# pcb.net
KiCad netlist of a schematic drawn in EAGLE
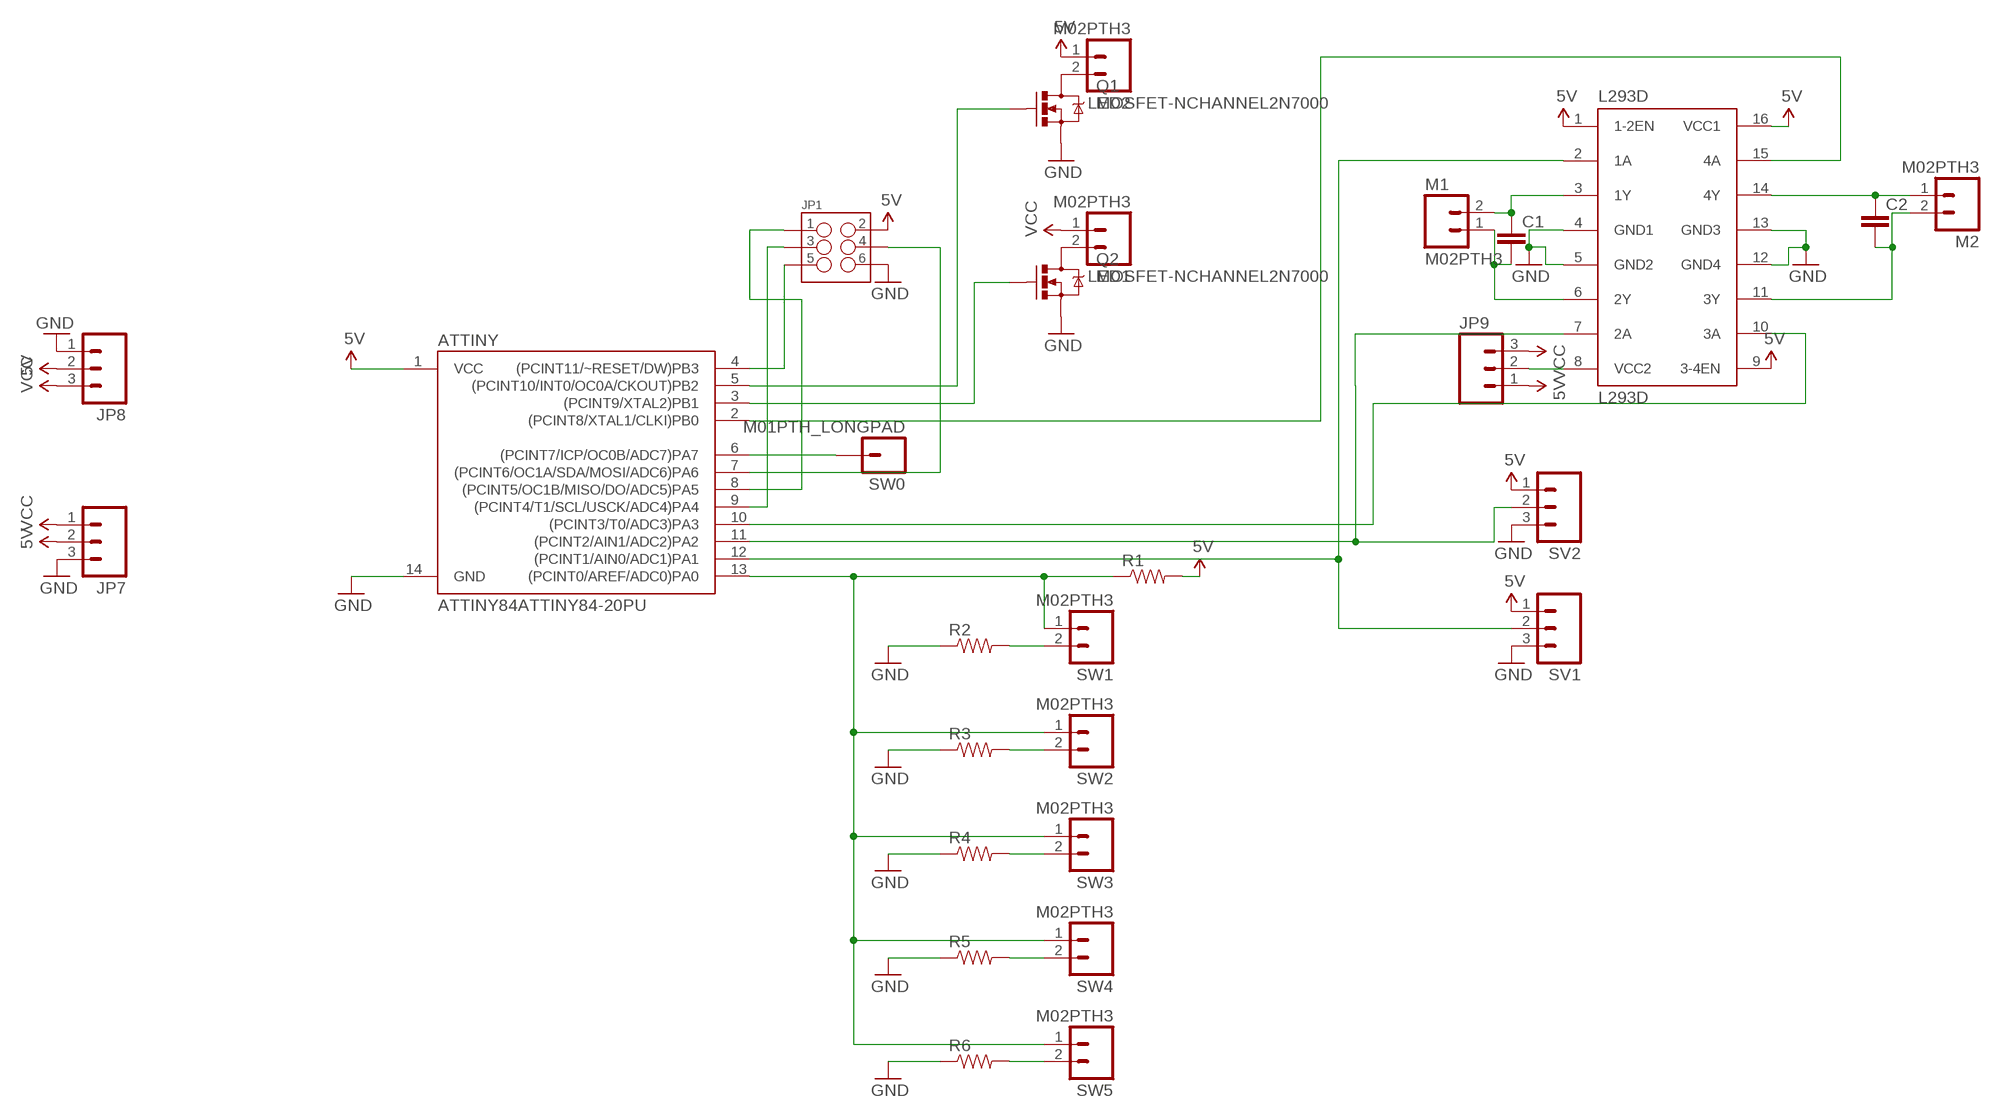
[diagram p0: schematic, sheet 1]

(export (version "E")
  (design (tool "Eeschema 10.0.6"))
  (components
    (comp (ref "ATTINY")
      (value "ATTINY84ATTINY84-20PU")
      (footprint "eagle-import:DIL14")
      (libsource (lib "eagle-import") (part "ATTINY84ATTINY84-20PU"))
    )
    (comp (ref "C1")
      (value "CAPPTH")
      (footprint "eagle-import:CAP-PTH-SMALL")
      (libsource (lib "eagle-import") (part "CAPPTH"))
    )
    (comp (ref "C2")
      (value "CAPPTH")
      (footprint "eagle-import:CAP-PTH-SMALL")
      (libsource (lib "eagle-import") (part "CAPPTH"))
    )
    (comp (ref "JP1")
      (value "M03X22X3_SILK_MALE_PTH")
      (footprint "eagle-import:2X3")
      (libsource (lib "eagle-import") (part "M03X22X3_SILK_MALE_PTH"))
    )
    (comp (ref "JP7")
      (value "M03SCREW")
      (footprint "eagle-import:SCREWTERMINAL-3.5MM-3")
      (libsource (lib "eagle-import") (part "M03SCREW"))
    )
    (comp (ref "JP8")
      (value "M03SCREW")
      (footprint "eagle-import:SCREWTERMINAL-3.5MM-3")
      (libsource (lib "eagle-import") (part "M03SCREW"))
    )
    (comp (ref "JP9")
      (value "M03LONGPADS")
      (footprint "eagle-import:1X03_LONGPADS")
      (libsource (lib "eagle-import") (part "M03LONGPADS"))
    )
    (comp (ref "L293D")
      (value "L293D")
      (footprint "eagle-import:DIL16")
      (libsource (lib "eagle-import") (part "L293D"))
    )
    (comp (ref "LED1")
      (value "M02PTH3")
      (footprint "eagle-import:1X02_LONGPADS")
      (libsource (lib "eagle-import") (part "M02PTH3"))
    )
    (comp (ref "LED2")
      (value "M02PTH3")
      (footprint "eagle-import:1X02_LONGPADS")
      (libsource (lib "eagle-import") (part "M02PTH3"))
    )
    (comp (ref "M1")
      (value "M02PTH3")
      (footprint "eagle-import:1X02_LONGPADS")
      (libsource (lib "eagle-import") (part "M02PTH3"))
    )
    (comp (ref "M2")
      (value "M02PTH3")
      (footprint "eagle-import:1X02_LONGPADS")
      (libsource (lib "eagle-import") (part "M02PTH3"))
    )
    (comp (ref "Q1")
      (value "MOSFET-NCHANNEL2N7000")
      (footprint "eagle-import:TO-92")
      (libsource (lib "eagle-import") (part "MOSFET-NCHANNEL2N7000"))
    )
    (comp (ref "Q2")
      (value "MOSFET-NCHANNEL2N7000")
      (footprint "eagle-import:TO-92")
      (libsource (lib "eagle-import") (part "MOSFET-NCHANNEL2N7000"))
    )
    (comp (ref "R1")
      (value "RESISTORPTH-1/4W")
      (footprint "eagle-import:AXIAL-0.4")
      (libsource (lib "eagle-import") (part "RESISTORPTH-1/4W"))
    )
    (comp (ref "R2")
      (value "RESISTORPTH-1/4W")
      (footprint "eagle-import:AXIAL-0.4")
      (libsource (lib "eagle-import") (part "RESISTORPTH-1/4W"))
    )
    (comp (ref "R3")
      (value "RESISTORPTH-1/4W")
      (footprint "eagle-import:AXIAL-0.4")
      (libsource (lib "eagle-import") (part "RESISTORPTH-1/4W"))
    )
    (comp (ref "R4")
      (value "RESISTORPTH-1/4W")
      (footprint "eagle-import:AXIAL-0.4")
      (libsource (lib "eagle-import") (part "RESISTORPTH-1/4W"))
    )
    (comp (ref "R5")
      (value "RESISTORPTH-1/4W")
      (footprint "eagle-import:AXIAL-0.4")
      (libsource (lib "eagle-import") (part "RESISTORPTH-1/4W"))
    )
    (comp (ref "R6")
      (value "RESISTORPTH-1/4W")
      (footprint "eagle-import:AXIAL-0.4")
      (libsource (lib "eagle-import") (part "RESISTORPTH-1/4W"))
    )
    (comp (ref "SV1")
      (value "M03LONGPADS")
      (footprint "eagle-import:1X03_LONGPADS")
      (libsource (lib "eagle-import") (part "M03LONGPADS"))
    )
    (comp (ref "SV2")
      (value "M03LONGPADS")
      (footprint "eagle-import:1X03_LONGPADS")
      (libsource (lib "eagle-import") (part "M03LONGPADS"))
    )
    (comp (ref "SW0")
      (value "M01PTH_LONGPAD")
      (footprint "eagle-import:1X01_LONGPAD")
      (libsource (lib "eagle-import") (part "M01PTH_LONGPAD"))
    )
    (comp (ref "SW1")
      (value "M02PTH3")
      (footprint "eagle-import:1X02_LONGPADS")
      (libsource (lib "eagle-import") (part "M02PTH3"))
    )
    (comp (ref "SW2")
      (value "M02PTH3")
      (footprint "eagle-import:1X02_LONGPADS")
      (libsource (lib "eagle-import") (part "M02PTH3"))
    )
    (comp (ref "SW3")
      (value "M02PTH3")
      (footprint "eagle-import:1X02_LONGPADS")
      (libsource (lib "eagle-import") (part "M02PTH3"))
    )
    (comp (ref "SW4")
      (value "M02PTH3")
      (footprint "eagle-import:1X02_LONGPADS")
      (libsource (lib "eagle-import") (part "M02PTH3"))
    )
    (comp (ref "SW5")
      (value "M02PTH3")
      (footprint "eagle-import:1X02_LONGPADS")
      (libsource (lib "eagle-import") (part "M02PTH3"))
    )
  )
  (nets
    (net (code "1") (name "5V") (class "Default")
      (node (ref "ATTINY") (pin "1") (pinfunction "VCC_1") (pintype "bidirectional"))
      (node (ref "JP1") (pin "2") (pinfunction "2_2") (pintype "bidirectional"))
      (node (ref "JP7") (pin "2") (pinfunction "2_2") (pintype "passive"))
      (node (ref "JP8") (pin "2") (pinfunction "2_2") (pintype "passive"))
      (node (ref "JP9") (pin "1") (pinfunction "1_1") (pintype "passive"))
      (node (ref "L293D") (pin "1") (pinfunction "1-2EN_1") (pintype "input"))
      (node (ref "L293D") (pin "16") (pinfunction "VCC1_16") (pintype "power_in"))
      (node (ref "L293D") (pin "9") (pinfunction "3-4EN_9") (pintype "input"))
      (node (ref "LED2") (pin "1") (pinfunction "1_1") (pintype "passive"))
      (node (ref "R1") (pin "P$2") (pinfunction "2_P$2") (pintype "passive"))
      (node (ref "SV1") (pin "1") (pinfunction "1_1") (pintype "passive"))
      (node (ref "SV2") (pin "1") (pinfunction "1_1") (pintype "passive"))
    )
    (net (code "2") (name "GND") (class "Default")
      (node (ref "ATTINY") (pin "14") (pinfunction "GND_14") (pintype "bidirectional"))
      (node (ref "JP1") (pin "6") (pinfunction "6_6") (pintype "bidirectional"))
      (node (ref "JP7") (pin "3") (pinfunction "3_3") (pintype "passive"))
      (node (ref "JP8") (pin "1") (pinfunction "1_1") (pintype "passive"))
      (node (ref "L293D") (pin "12") (pinfunction "GND4_12") (pintype "power_in"))
      (node (ref "L293D") (pin "13") (pinfunction "GND3_13") (pintype "power_in"))
      (node (ref "L293D") (pin "4") (pinfunction "GND1_4") (pintype "power_in"))
      (node (ref "L293D") (pin "5") (pinfunction "GND2_5") (pintype "power_in"))
      (node (ref "Q1") (pin "1") (pinfunction "S_1") (pintype "passive"))
      (node (ref "Q2") (pin "1") (pinfunction "S_1") (pintype "passive"))
      (node (ref "R2") (pin "P$1") (pinfunction "1_P$1") (pintype "passive"))
      (node (ref "R3") (pin "P$1") (pinfunction "1_P$1") (pintype "passive"))
      (node (ref "R4") (pin "P$1") (pinfunction "1_P$1") (pintype "passive"))
      (node (ref "R5") (pin "P$1") (pinfunction "1_P$1") (pintype "passive"))
      (node (ref "R6") (pin "P$1") (pinfunction "1_P$1") (pintype "passive"))
      (node (ref "SV1") (pin "3") (pinfunction "3_3") (pintype "passive"))
      (node (ref "SV2") (pin "3") (pinfunction "3_3") (pintype "passive"))
    )
    (net (code "3") (name "Net-(ATTINY-(PCINT0{slash}AREF{slash}ADC0)PA0)") (class "Default")
      (node (ref "ATTINY") (pin "13") (pinfunction "(PCINT0/AREF/ADC0)PA0_13") (pintype "bidirectional"))
      (node (ref "R1") (pin "P$1") (pinfunction "1_P$1") (pintype "passive"))
      (node (ref "SW1") (pin "1") (pinfunction "1_1") (pintype "passive"))
      (node (ref "SW2") (pin "1") (pinfunction "1_1") (pintype "passive"))
      (node (ref "SW3") (pin "1") (pinfunction "1_1") (pintype "passive"))
      (node (ref "SW4") (pin "1") (pinfunction "1_1") (pintype "passive"))
      (node (ref "SW5") (pin "1") (pinfunction "1_1") (pintype "passive"))
    )
    (net (code "4") (name "Net-(ATTINY-(PCINT1{slash}AIN0{slash}ADC1)PA1)") (class "Default")
      (node (ref "ATTINY") (pin "12") (pinfunction "(PCINT1/AIN0/ADC1)PA1_12") (pintype "bidirectional"))
      (node (ref "L293D") (pin "2") (pinfunction "1A_2") (pintype "input"))
      (node (ref "SV1") (pin "2") (pinfunction "2_2") (pintype "passive"))
    )
    (net (code "5") (name "Net-(ATTINY-(PCINT2{slash}AIN1{slash}ADC2)PA2)") (class "Default")
      (node (ref "ATTINY") (pin "11") (pinfunction "(PCINT2/AIN1/ADC2)PA2_11") (pintype "bidirectional"))
      (node (ref "L293D") (pin "7") (pinfunction "2A_7") (pintype "input"))
      (node (ref "SV2") (pin "2") (pinfunction "2_2") (pintype "passive"))
    )
    (net (code "6") (name "Net-(ATTINY-(PCINT3{slash}T0{slash}ADC3)PA3)") (class "Default")
      (node (ref "ATTINY") (pin "10") (pinfunction "(PCINT3/T0/ADC3)PA3_10") (pintype "bidirectional"))
      (node (ref "L293D") (pin "10") (pinfunction "3A_10") (pintype "input"))
    )
    (net (code "7") (name "Net-(ATTINY-(PCINT4{slash}T1{slash}SCL{slash}USCK{slash}ADC4)PA4)") (class "Default")
      (node (ref "ATTINY") (pin "9") (pinfunction "(PCINT4/T1/SCL/USCK/ADC4)PA4_9") (pintype "bidirectional"))
      (node (ref "JP1") (pin "3") (pinfunction "3_3") (pintype "bidirectional"))
    )
    (net (code "8") (name "Net-(ATTINY-(PCINT5{slash}OC1B{slash}MISO{slash}DO{slash}ADC5)PA5)") (class "Default")
      (node (ref "ATTINY") (pin "8") (pinfunction "(PCINT5/OC1B/MISO/DO/ADC5)PA5_8") (pintype "bidirectional"))
      (node (ref "JP1") (pin "1") (pinfunction "1_1") (pintype "bidirectional"))
    )
    (net (code "9") (name "Net-(ATTINY-(PCINT6{slash}OC1A{slash}SDA{slash}MOSI{slash}ADC6)PA6)") (class "Default")
      (node (ref "ATTINY") (pin "7") (pinfunction "(PCINT6/OC1A/SDA/MOSI/ADC6)PA6_7") (pintype "bidirectional"))
      (node (ref "JP1") (pin "4") (pinfunction "4_4") (pintype "bidirectional"))
    )
    (net (code "10") (name "Net-(ATTINY-(PCINT7{slash}ICP{slash}OC0B{slash}ADC7)PA7)") (class "Default")
      (node (ref "ATTINY") (pin "6") (pinfunction "(PCINT7/ICP/OC0B/ADC7)PA7_6") (pintype "bidirectional"))
      (node (ref "SW0") (pin "1") (pinfunction "1_1") (pintype "passive"))
    )
    (net (code "11") (name "Net-(ATTINY-(PCINT8{slash}XTAL1{slash}CLKI)PB0)") (class "Default")
      (node (ref "ATTINY") (pin "2") (pinfunction "(PCINT8/XTAL1/CLKI)PB0_2") (pintype "bidirectional"))
      (node (ref "L293D") (pin "15") (pinfunction "4A_15") (pintype "input"))
    )
    (net (code "12") (name "Net-(ATTINY-(PCINT9{slash}XTAL2)PB1)") (class "Default")
      (node (ref "ATTINY") (pin "3") (pinfunction "(PCINT9/XTAL2)PB1_3") (pintype "bidirectional"))
      (node (ref "Q2") (pin "2") (pinfunction "G_2") (pintype "passive"))
    )
    (net (code "13") (name "Net-(ATTINY-(PCINT10{slash}INT0{slash}OC0A{slash}CKOUT)PB2)") (class "Default")
      (node (ref "ATTINY") (pin "5") (pinfunction "(PCINT10/INT0/OC0A/CKOUT)PB2_5") (pintype "bidirectional"))
      (node (ref "Q1") (pin "2") (pinfunction "G_2") (pintype "passive"))
    )
    (net (code "14") (name "Net-(ATTINY-(PCINT11{slash}~{RESET{slash}DW})PB3)") (class "Default")
      (node (ref "ATTINY") (pin "4") (pinfunction "(PCINT11/~{RESET/DW})PB3_4") (pintype "bidirectional"))
      (node (ref "JP1") (pin "5") (pinfunction "5_5") (pintype "bidirectional"))
    )
    (net (code "15") (name "Net-(L293D-1Y)") (class "Default")
      (node (ref "C1") (pin "1") (pinfunction "1_1") (pintype "passive"))
      (node (ref "L293D") (pin "3") (pinfunction "1Y_3") (pintype "output"))
      (node (ref "M1") (pin "2") (pinfunction "2_2") (pintype "passive"))
    )
    (net (code "16") (name "Net-(L293D-2Y)") (class "Default")
      (node (ref "C1") (pin "2") (pinfunction "2_2") (pintype "passive"))
      (node (ref "L293D") (pin "6") (pinfunction "2Y_6") (pintype "output"))
      (node (ref "M1") (pin "1") (pinfunction "1_1") (pintype "passive"))
    )
    (net (code "17") (name "Net-(L293D-3Y)") (class "Default")
      (node (ref "C2") (pin "2") (pinfunction "2_2") (pintype "passive"))
      (node (ref "L293D") (pin "11") (pinfunction "3Y_11") (pintype "output"))
      (node (ref "M2") (pin "2") (pinfunction "2_2") (pintype "passive"))
    )
    (net (code "18") (name "Net-(L293D-4Y)") (class "Default")
      (node (ref "C2") (pin "1") (pinfunction "1_1") (pintype "passive"))
      (node (ref "L293D") (pin "14") (pinfunction "4Y_14") (pintype "output"))
      (node (ref "M2") (pin "1") (pinfunction "1_1") (pintype "passive"))
    )
    (net (code "19") (name "Net-(L293D-VCC2)") (class "Default")
      (node (ref "JP9") (pin "2") (pinfunction "2_2") (pintype "passive"))
      (node (ref "L293D") (pin "8") (pinfunction "VCC2_8") (pintype "power_in"))
    )
    (net (code "20") (name "Net-(Q1-D)") (class "Default")
      (node (ref "LED2") (pin "2") (pinfunction "2_2") (pintype "passive"))
      (node (ref "Q1") (pin "3") (pinfunction "D_3") (pintype "passive"))
    )
    (net (code "21") (name "Net-(Q2-D)") (class "Default")
      (node (ref "LED1") (pin "2") (pinfunction "2_2") (pintype "passive"))
      (node (ref "Q2") (pin "3") (pinfunction "D_3") (pintype "passive"))
    )
    (net (code "22") (name "Net-(R2-2)") (class "Default")
      (node (ref "R2") (pin "P$2") (pinfunction "2_P$2") (pintype "passive"))
      (node (ref "SW1") (pin "2") (pinfunction "2_2") (pintype "passive"))
    )
    (net (code "23") (name "Net-(R3-2)") (class "Default")
      (node (ref "R3") (pin "P$2") (pinfunction "2_P$2") (pintype "passive"))
      (node (ref "SW2") (pin "2") (pinfunction "2_2") (pintype "passive"))
    )
    (net (code "24") (name "Net-(R4-2)") (class "Default")
      (node (ref "R4") (pin "P$2") (pinfunction "2_P$2") (pintype "passive"))
      (node (ref "SW3") (pin "2") (pinfunction "2_2") (pintype "passive"))
    )
    (net (code "25") (name "Net-(R5-2)") (class "Default")
      (node (ref "R5") (pin "P$2") (pinfunction "2_P$2") (pintype "passive"))
      (node (ref "SW4") (pin "2") (pinfunction "2_2") (pintype "passive"))
    )
    (net (code "26") (name "Net-(R6-2)") (class "Default")
      (node (ref "R6") (pin "P$2") (pinfunction "2_P$2") (pintype "passive"))
      (node (ref "SW5") (pin "2") (pinfunction "2_2") (pintype "passive"))
    )
    (net (code "27") (name "VCC") (class "Default")
      (node (ref "JP7") (pin "1") (pinfunction "1_1") (pintype "passive"))
      (node (ref "JP8") (pin "3") (pinfunction "3_3") (pintype "passive"))
      (node (ref "JP9") (pin "3") (pinfunction "3_3") (pintype "passive"))
      (node (ref "LED1") (pin "1") (pinfunction "1_1") (pintype "passive"))
    )
  )
)
